# G-103M-20190827.net
KiCad netlist of a schematic drawn in Altium Designer
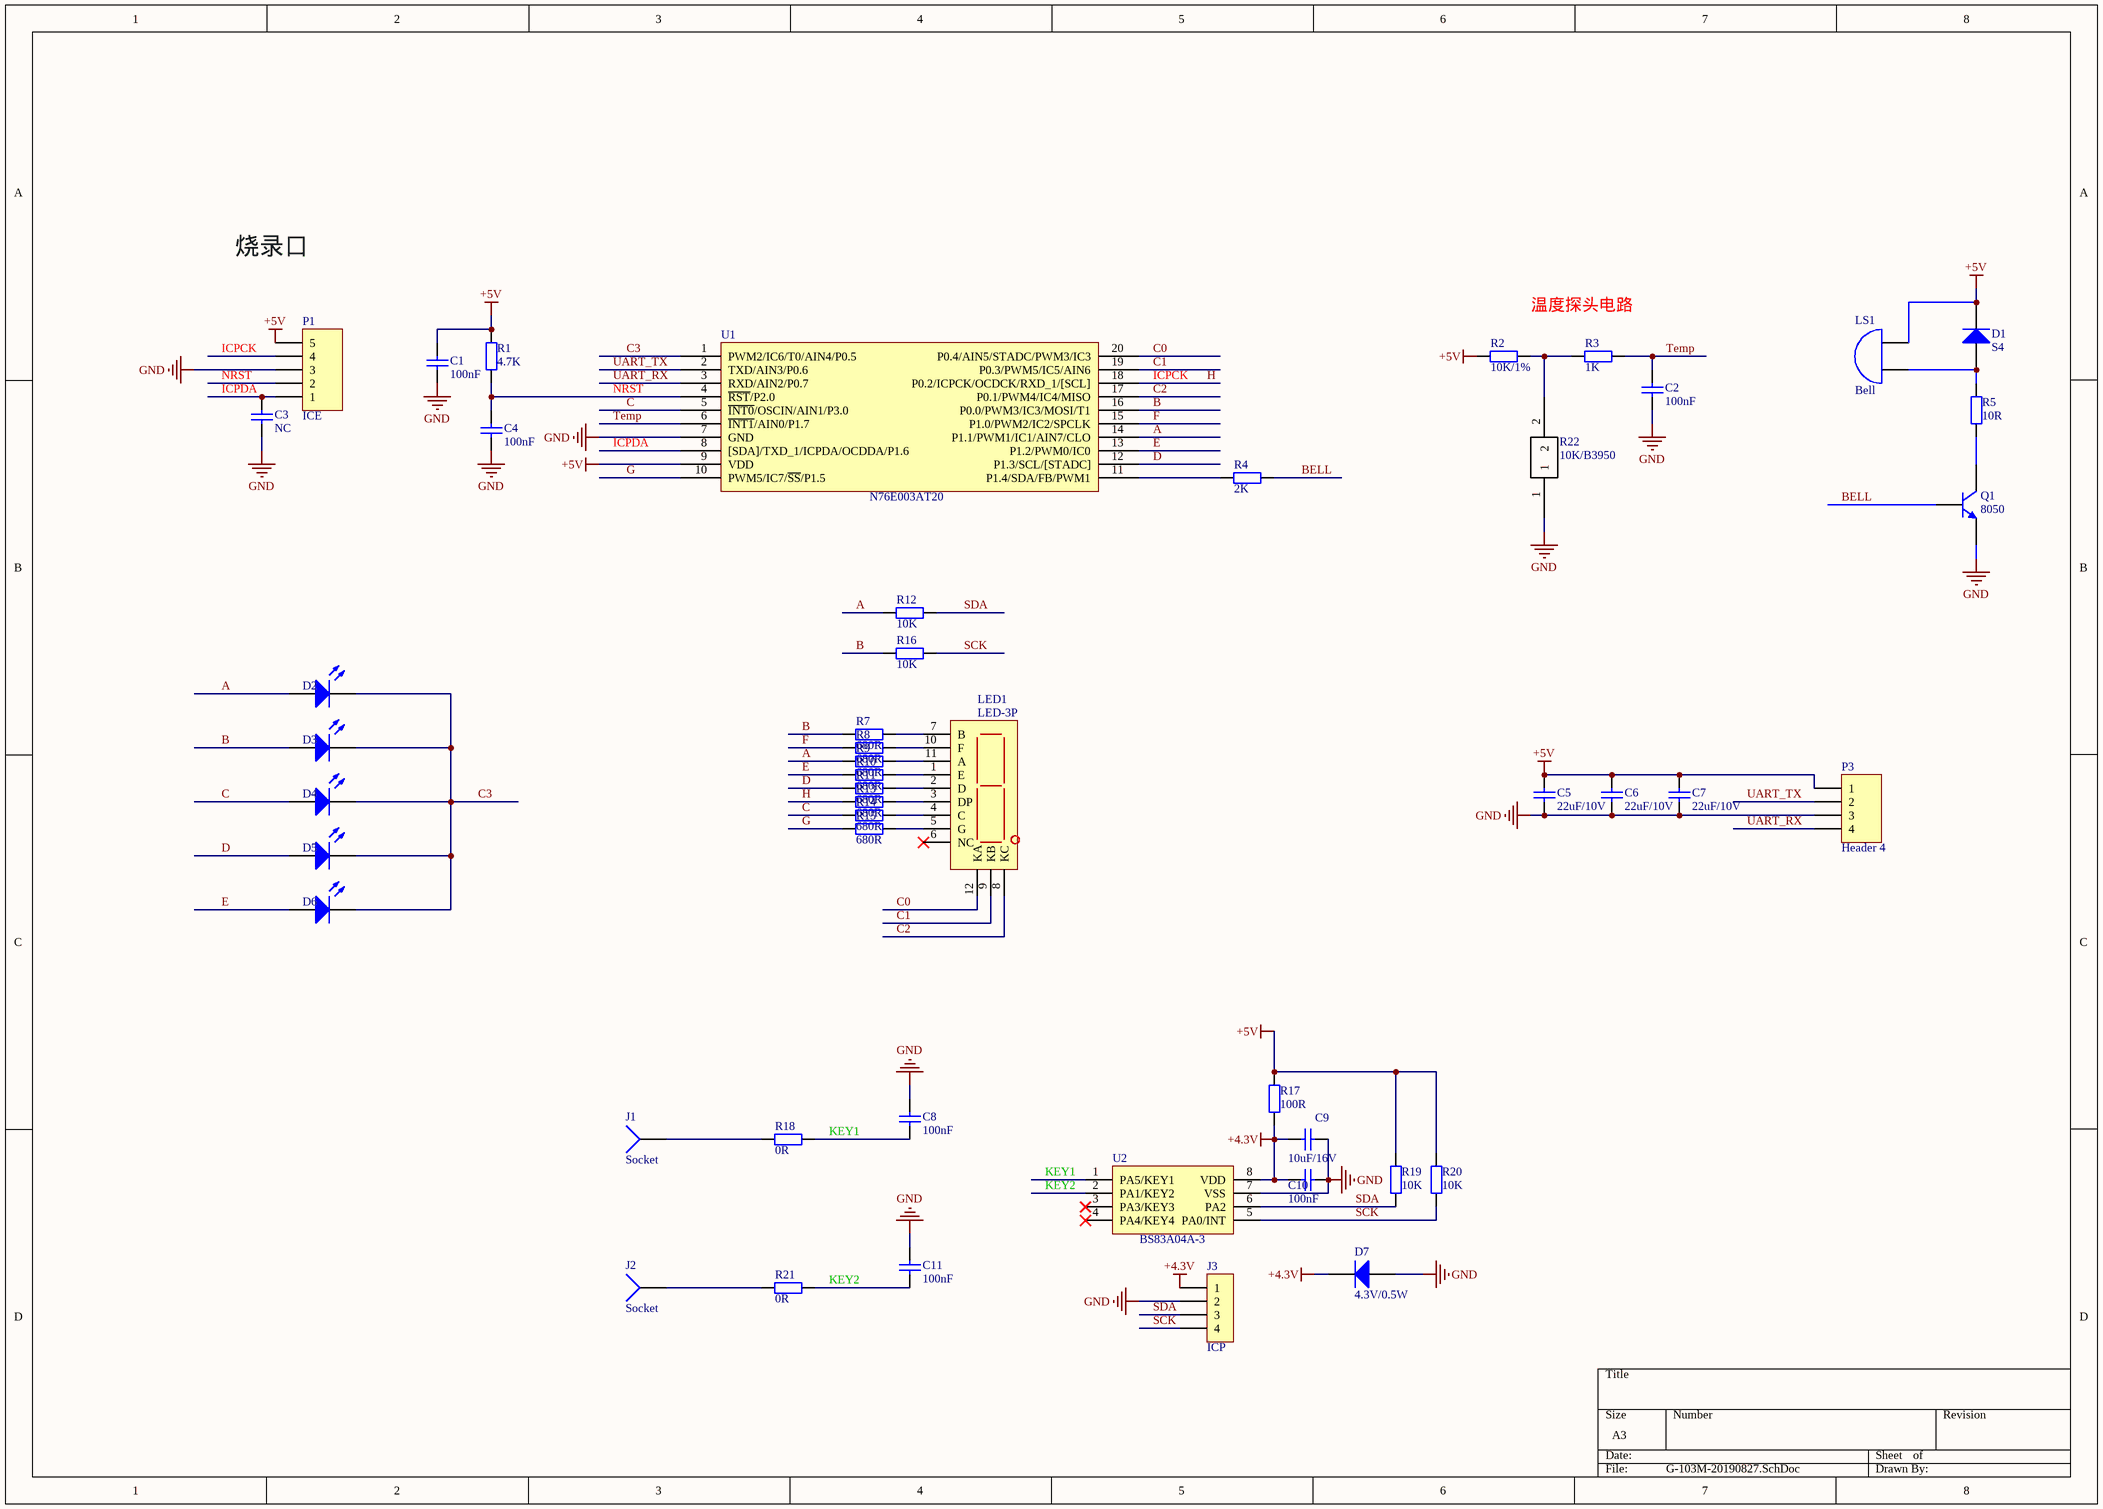
[diagram p0: G-103M-20190827.SchDoc]

(export (version "E")
  (design (tool "Eeschema 10.0.6"))
  (components
    (comp (ref "C1")
      (value "100nF")
      (footprint "SMD-0603")
      (description "Capacitor")
      (fields (field (name "Comment") "Cap") (field (name "PUBLISHER") "Altium Limited"))
      (libsource (lib "Miscellaneous Devices") (part "Cap"))
    )
    (comp (ref "C2")
      (value "100nF")
      (footprint "SMD-0603")
      (description "Capacitor")
      (fields (field (name "PUBLISHER") "Altium Limited"))
      (libsource (lib "Miscellaneous Devices") (part "Cap"))
    )
    (comp (ref "C3")
      (value "NC")
      (footprint "SMD-0603")
      (description "Capacitor")
      (fields (field (name "PUBLISHER") "Altium Limited"))
      (libsource (lib "Miscellaneous Devices") (part "Cap"))
    )
    (comp (ref "C4")
      (value "100nF")
      (footprint "SMD-0603")
      (description "Capacitor")
      (fields (field (name "Comment") "Cap") (field (name "PUBLISHER") "Altium Limited"))
      (libsource (lib "Miscellaneous Devices") (part "Cap"))
    )
    (comp (ref "C5")
      (value "22uF/10V")
      (footprint "SMD-0603")
      (description "Capacitor")
      (fields (field (name "PUBLISHER") "Altium Limited"))
      (libsource (lib "Miscellaneous Devices") (part "Cap"))
    )
    (comp (ref "C6")
      (value "22uF/10V")
      (footprint "SMD-0603")
      (description "Capacitor")
      (fields (field (name "PUBLISHER") "Altium Limited"))
      (libsource (lib "Miscellaneous Devices") (part "Cap"))
    )
    (comp (ref "C7")
      (value "22uF/10V")
      (footprint "SMD-0603")
      (description "Capacitor")
      (fields (field (name "PUBLISHER") "Altium Limited"))
      (libsource (lib "Miscellaneous Devices") (part "Cap"))
    )
    (comp (ref "C8")
      (value "100nF")
      (footprint "SMD-0603")
      (description "Capacitor (Semiconductor SIM Model)")
      (fields (field (name "PUBLISHER") "Altium Limited"))
      (libsource (lib "Miscellaneous Devices") (part "Cap Semi"))
    )
    (comp (ref "C9")
      (value "10uF/16V")
      (footprint "SMD-0603")
      (description "Capacitor (Semiconductor SIM Model)")
      (fields (field (name "PUBLISHER") "Altium Limited"))
      (libsource (lib "Miscellaneous Devices") (part "Cap Semi"))
    )
    (comp (ref "C10")
      (value "100nF")
      (footprint "SMD-0603")
      (description "Capacitor (Semiconductor SIM Model)")
      (fields (field (name "PUBLISHER") "Altium Limited"))
      (libsource (lib "Miscellaneous Devices") (part "Cap Semi"))
    )
    (comp (ref "C11")
      (value "100nF")
      (footprint "SMD-0603")
      (description "Capacitor (Semiconductor SIM Model)")
      (fields (field (name "PUBLISHER") "Altium Limited"))
      (libsource (lib "Miscellaneous Devices") (part "Cap Semi"))
    )
    (comp (ref "D1")
      (value "S4")
      (footprint "SOD123")
      (description "1 Amp General Purpose Rectifier")
      (fields (field (name "PUBLISHER") "Altium Limited"))
      (libsource (lib "Miscellaneous Devices") (part "Diode 1N4007"))
    )
    (comp (ref "D2")
      (value "~")
      (footprint "LED-3MM")
      (description "Typical RED GaAs LED")
      (fields (field (name "PUBLISHER") "Altium Limited"))
      (libsource (lib "Miscellaneous Devices") (part "LED1"))
    )
    (comp (ref "D3")
      (value "~")
      (footprint "LED-3MM")
      (description "Typical RED GaAs LED")
      (fields (field (name "PUBLISHER") "Altium Limited"))
      (libsource (lib "Miscellaneous Devices") (part "LED1"))
    )
    (comp (ref "D4")
      (value "~")
      (footprint "LED-3MM")
      (description "Typical RED GaAs LED")
      (fields (field (name "PUBLISHER") "Altium Limited"))
      (libsource (lib "Miscellaneous Devices") (part "LED1"))
    )
    (comp (ref "D5")
      (value "~")
      (footprint "LED-3MM")
      (description "Typical RED GaAs LED")
      (fields (field (name "PUBLISHER") "Altium Limited"))
      (libsource (lib "Miscellaneous Devices") (part "LED1"))
    )
    (comp (ref "D6")
      (value "~")
      (footprint "LED-3MM")
      (description "Typical RED GaAs LED")
      (fields (field (name "PUBLISHER") "Altium Limited"))
      (libsource (lib "Miscellaneous Devices") (part "LED1"))
    )
    (comp (ref "D7")
      (value "4.3V/0.5W")
      (footprint "SOD123")
      (description "1 Amp General Purpose Rectifier")
      (fields (field (name "PUBLISHER") "Altium Limited"))
      (libsource (lib "Miscellaneous Devices") (part "Diode 1N4007"))
    )
    (comp (ref "J1")
      (value "Socket")
      (footprint "KEY-C1")
      (fields (field (name "PUBLISHER") "Altium Limited"))
      (libsource (lib "Miscellaneous Connectors") (part "Socket"))
    )
    (comp (ref "J2")
      (value "Socket")
      (footprint "KEY-C1")
      (fields (field (name "PUBLISHER") "Altium Limited"))
      (libsource (lib "Miscellaneous Connectors") (part "Socket"))
    )
    (comp (ref "J3")
      (value "ICP")
      (footprint "HDR1X4")
      (description "Connector")
      (libsource (lib "SCH") (part "CON4"))
    )
    (comp (ref "LED1")
      (value "LED-3P")
      (footprint "LED363")
      (description "LED")
      (libsource (lib "MJRS0-20150109") (part "LED-3P"))
    )
    (comp (ref "LS1")
      (value "Bell")
      (footprint "BUZ-2-5V")
      (description "Electrical Bell")
      (fields (field (name "PUBLISHER") "Altium Limited"))
      (libsource (lib "Miscellaneous Devices") (part "Bell"))
    )
    (comp (ref "P1")
      (value "ICE")
      (footprint "HDR1X5")
      (description "Header, 5-Pin")
      (fields (field (name "PUBLISHER") "Altium Limited"))
      (libsource (lib "Miscellaneous Connectors") (part "Header 5"))
    )
    (comp (ref "P3")
      (value "Header 4")
      (footprint "2.0-4P")
      (description "Header, 4-Pin")
      (fields (field (name "PUBLISHER") "Altium Limited"))
      (libsource (lib "Miscellaneous Connectors") (part "Header 4"))
    )
    (comp (ref "Q1")
      (value "8050")
      (footprint "SOT-23E2")
      (description "NPN General Purpose Amplifier")
      (fields (field (name "PUBLISHER") "Altium Limited"))
      (libsource (lib "接收机") (part "2N3904"))
    )
    (comp (ref "R1")
      (value "4.7K")
      (footprint "SMD-0603")
      (description "Resistor")
      (fields (field (name "Comment") "Res2") (field (name "PUBLISHER") "Altium Limited"))
      (libsource (lib "") (part "Res2_3"))
    )
    (comp (ref "R2")
      (value "10K/1%")
      (footprint "SMD-0603")
      (description "Resistor")
      (fields (field (name "PUBLISHER") "Altium Limited"))
      (libsource (lib "Miscellaneous Devices") (part "Res2"))
    )
    (comp (ref "R3")
      (value "1K")
      (footprint "SMD-0603")
      (description "Resistor")
      (fields (field (name "PUBLISHER") "Altium Limited"))
      (libsource (lib "Miscellaneous Devices") (part "Res2"))
    )
    (comp (ref "R4")
      (value "2K")
      (footprint "SMD-0603")
      (description "Resistor")
      (fields (field (name "PUBLISHER") "Altium Limited"))
      (libsource (lib "Miscellaneous Devices") (part "Res2"))
    )
    (comp (ref "R5")
      (value "10R")
      (footprint "SMD-0603")
      (description "Resistor")
      (fields (field (name "PUBLISHER") "Altium Limited"))
      (libsource (lib "") (part "Res2_3"))
    )
    (comp (ref "R7")
      (value "680R")
      (footprint "SMD-0603")
      (description "Resistor")
      (fields (field (name "PUBLISHER") "Altium Limited"))
      (libsource (lib "Miscellaneous Devices") (part "Res2"))
    )
    (comp (ref "R8")
      (value "680R")
      (footprint "SMD-0603")
      (description "Resistor")
      (fields (field (name "PUBLISHER") "Altium Limited"))
      (libsource (lib "Miscellaneous Devices") (part "Res2"))
    )
    (comp (ref "R9")
      (value "680R")
      (footprint "SMD-0603")
      (description "Resistor")
      (fields (field (name "PUBLISHER") "Altium Limited"))
      (libsource (lib "Miscellaneous Devices") (part "Res2"))
    )
    (comp (ref "R10")
      (value "680R")
      (footprint "SMD-0603")
      (description "Resistor")
      (fields (field (name "PUBLISHER") "Altium Limited"))
      (libsource (lib "Miscellaneous Devices") (part "Res2"))
    )
    (comp (ref "R11")
      (value "680R")
      (footprint "SMD-0603")
      (description "Resistor")
      (fields (field (name "PUBLISHER") "Altium Limited"))
      (libsource (lib "Miscellaneous Devices") (part "Res2"))
    )
    (comp (ref "R12")
      (value "10K")
      (footprint "SMD-0603")
      (description "Resistor")
      (fields (field (name "PUBLISHER") "Altium Limited"))
      (libsource (lib "") (part "Res2_2"))
    )
    (comp (ref "R13")
      (value "680R")
      (footprint "SMD-0603")
      (description "Resistor")
      (fields (field (name "PUBLISHER") "Altium Limited"))
      (libsource (lib "Miscellaneous Devices") (part "Res2"))
    )
    (comp (ref "R14")
      (value "680R")
      (footprint "SMD-0603")
      (description "Resistor")
      (fields (field (name "PUBLISHER") "Altium Limited"))
      (libsource (lib "Miscellaneous Devices") (part "Res2"))
    )
    (comp (ref "R15")
      (value "680R")
      (footprint "SMD-0603")
      (description "Resistor")
      (fields (field (name "PUBLISHER") "Altium Limited"))
      (libsource (lib "Miscellaneous Devices") (part "Res2"))
    )
    (comp (ref "R16")
      (value "10K")
      (footprint "SMD-0603")
      (description "Resistor")
      (fields (field (name "PUBLISHER") "Altium Limited"))
      (libsource (lib "") (part "Res2_2"))
    )
    (comp (ref "R17")
      (value "100R")
      (footprint "SMD-0603")
      (description "Resistor")
      (fields (field (name "PUBLISHER") "Altium Limited"))
      (libsource (lib "") (part "Res2_3"))
    )
    (comp (ref "R18")
      (value "0R")
      (footprint "SMD-0603")
      (description "Resistor")
      (fields (field (name "PUBLISHER") "Altium Limited"))
      (libsource (lib "Miscellaneous Devices") (part "Res2"))
    )
    (comp (ref "R19")
      (value "10K")
      (footprint "SMD-0603")
      (description "Resistor")
      (fields (field (name "PUBLISHER") "Altium Limited"))
      (libsource (lib "") (part "Res2_1"))
    )
    (comp (ref "R20")
      (value "10K")
      (footprint "SMD-0603")
      (description "Resistor")
      (fields (field (name "PUBLISHER") "Altium Limited"))
      (libsource (lib "") (part "Res2_1"))
    )
    (comp (ref "R21")
      (value "0R")
      (footprint "SMD-0603")
      (description "Resistor")
      (fields (field (name "PUBLISHER") "Altium Limited"))
      (libsource (lib "Miscellaneous Devices") (part "Res2"))
    )
    (comp (ref "R22")
      (value "10K/B3950")
      (footprint "SMD-0603")
      (libsource (lib "Integrated_Library") (part "10K/B3950"))
    )
    (comp (ref "U1")
      (value "N76E003AT20")
      (footprint "TSSOP-20")
      (libsource (lib "AQ405_Power") (part "N76E003AT20"))
    )
    (comp (ref "U2") (value "BS83A04A-3") (footprint "SOP8") (libsource (lib "SCH") (part "BS83A04A-3")))
  )
  (nets
    (net (code "1") (name "+4.3V") (class "Default")
      (node (ref "C10") (pin "1") (pinfunction "1_1") (pintype "passive"))
      (node (ref "C9") (pin "1") (pinfunction "1_1") (pintype "passive"))
      (node (ref "D7") (pin "2") (pinfunction "K_2") (pintype "passive"))
      (node (ref "J3") (pin "1") (pinfunction "1_1") (pintype "passive"))
      (node (ref "R17") (pin "2") (pinfunction "2_2") (pintype "passive"))
      (node (ref "U2") (pin "8") (pinfunction "VDD_8") (pintype "passive"))
    )
    (net (code "2") (name "+5V") (class "Default")
      (node (ref "C1") (pin "2") (pinfunction "2_2") (pintype "passive"))
      (node (ref "C5") (pin "2") (pinfunction "2_2") (pintype "passive"))
      (node (ref "C6") (pin "2") (pinfunction "2_2") (pintype "passive"))
      (node (ref "C7") (pin "2") (pinfunction "2_2") (pintype "passive"))
      (node (ref "D1") (pin "2") (pinfunction "K_2") (pintype "passive"))
      (node (ref "LS1") (pin "1") (pinfunction "A_1") (pintype "passive"))
      (node (ref "P1") (pin "5") (pinfunction "5_5") (pintype "passive"))
      (node (ref "P3") (pin "1") (pinfunction "1_1") (pintype "passive"))
      (node (ref "R1") (pin "1") (pinfunction "1_1") (pintype "passive"))
      (node (ref "R17") (pin "1") (pinfunction "1_1") (pintype "passive"))
      (node (ref "R19") (pin "2") (pinfunction "2_2") (pintype "passive"))
      (node (ref "R2") (pin "2") (pinfunction "2_2") (pintype "passive"))
      (node (ref "R20") (pin "2") (pinfunction "2_2") (pintype "passive"))
      (node (ref "U1") (pin "9") (pinfunction "VDD_9") (pintype "passive"))
    )
    (net (code "3") (name "/A") (class "Default")
      (node (ref "D2") (pin "1") (pinfunction "A_1") (pintype "passive"))
      (node (ref "R12") (pin "1") (pinfunction "1_1") (pintype "passive"))
      (node (ref "R9") (pin "2") (pinfunction "2_2") (pintype "passive"))
      (node (ref "U1") (pin "14") (pinfunction "P1.1/PWM1/IC1/AIN7/CLO_14") (pintype "passive"))
    )
    (net (code "4") (name "/B") (class "Default")
      (node (ref "D3") (pin "1") (pinfunction "A_1") (pintype "passive"))
      (node (ref "R16") (pin "1") (pinfunction "1_1") (pintype "passive"))
      (node (ref "R7") (pin "2") (pinfunction "2_2") (pintype "passive"))
      (node (ref "U1") (pin "16") (pinfunction "P0.0/PWM3/IC3/MOSI/T1_16") (pintype "passive"))
    )
    (net (code "5") (name "/BELL") (class "Default")
      (node (ref "Q1") (pin "B") (pinfunction "B_B") (pintype "passive"))
      (node (ref "R4") (pin "1") (pinfunction "1_1") (pintype "passive"))
    )
    (net (code "6") (name "/C") (class "Default")
      (node (ref "D4") (pin "1") (pinfunction "A_1") (pintype "passive"))
      (node (ref "R14") (pin "2") (pinfunction "2_2") (pintype "passive"))
      (node (ref "U1") (pin "5") (pinfunction "~{INT0}/OSCIN/AIN1/P3.0_5") (pintype "passive"))
    )
    (net (code "7") (name "/C0") (class "Default")
      (node (ref "LED1") (pin "12") (pinfunction "KA_12") (pintype "passive"))
      (node (ref "U1") (pin "20") (pinfunction "P0.4/AIN5/STADC/PWM3/IC3_20") (pintype "passive"))
    )
    (net (code "8") (name "/C1") (class "Default")
      (node (ref "LED1") (pin "9") (pinfunction "KB_9") (pintype "passive"))
      (node (ref "U1") (pin "19") (pinfunction "P0.3/PWM5/IC5/AIN6_19") (pintype "passive"))
    )
    (net (code "9") (name "/C2") (class "Default")
      (node (ref "LED1") (pin "8") (pinfunction "KC_8") (pintype "passive"))
      (node (ref "U1") (pin "17") (pinfunction "P0.1/PWM4/IC4/MISO_17") (pintype "passive"))
    )
    (net (code "10") (name "/C3") (class "Default")
      (node (ref "D2") (pin "2") (pinfunction "K_2") (pintype "passive"))
      (node (ref "D3") (pin "2") (pinfunction "K_2") (pintype "passive"))
      (node (ref "D4") (pin "2") (pinfunction "K_2") (pintype "passive"))
      (node (ref "D5") (pin "2") (pinfunction "K_2") (pintype "passive"))
      (node (ref "D6") (pin "2") (pinfunction "K_2") (pintype "passive"))
      (node (ref "U1") (pin "1") (pinfunction "PWM2/IC6/T0/AIN4/P0.5_1") (pintype "passive"))
    )
    (net (code "11") (name "/D") (class "Default")
      (node (ref "D5") (pin "1") (pinfunction "A_1") (pintype "passive"))
      (node (ref "R11") (pin "2") (pinfunction "2_2") (pintype "passive"))
      (node (ref "U1") (pin "12") (pinfunction "P1.3/SCL/[STADC]_12") (pintype "passive"))
    )
    (net (code "12") (name "/E") (class "Default")
      (node (ref "D6") (pin "1") (pinfunction "A_1") (pintype "passive"))
      (node (ref "R10") (pin "2") (pinfunction "2_2") (pintype "passive"))
      (node (ref "U1") (pin "13") (pinfunction "P1.2/PWM0/IC0_13") (pintype "passive"))
    )
    (net (code "13") (name "/F") (class "Default")
      (node (ref "R8") (pin "2") (pinfunction "2_2") (pintype "passive"))
      (node (ref "U1") (pin "15") (pinfunction "P1.0/PWM2/IC2/SPCLK_15") (pintype "passive"))
    )
    (net (code "14") (name "/G") (class "Default")
      (node (ref "R15") (pin "2") (pinfunction "2_2") (pintype "passive"))
      (node (ref "U1") (pin "10") (pinfunction "PWM5/IC7/~{SS}/P1.5_10") (pintype "passive"))
    )
    (net (code "15") (name "/H") (class "Default")
      (node (ref "P1") (pin "4") (pinfunction "4_4") (pintype "passive"))
      (node (ref "R13") (pin "2") (pinfunction "2_2") (pintype "passive"))
      (node (ref "U1") (pin "18") (pinfunction "P0.2/ICPCK/OCDCK/RXD_1/[SCL]_18") (pintype "passive"))
    )
    (net (code "16") (name "/ICPDA") (class "Default")
      (node (ref "C3") (pin "1") (pinfunction "1_1") (pintype "passive"))
      (node (ref "P1") (pin "1") (pinfunction "1_1") (pintype "passive"))
      (node (ref "U1") (pin "8") (pinfunction "[SDA]/TXD_1/ICPDA/OCDDA/P1.6_8") (pintype "passive"))
    )
    (net (code "17") (name "/KEY1") (class "Default")
      (node (ref "C8") (pin "1") (pinfunction "1_1") (pintype "passive"))
      (node (ref "R18") (pin "1") (pinfunction "1_1") (pintype "passive"))
      (node (ref "U2") (pin "1") (pinfunction "PA5/KEY1_1") (pintype "passive"))
    )
    (net (code "18") (name "/KEY2") (class "Default")
      (node (ref "C11") (pin "1") (pinfunction "1_1") (pintype "passive"))
      (node (ref "R21") (pin "1") (pinfunction "1_1") (pintype "passive"))
      (node (ref "U2") (pin "2") (pinfunction "PA1/KEY2_2") (pintype "passive"))
    )
    (net (code "19") (name "/NRST") (class "Default")
      (node (ref "C4") (pin "2") (pinfunction "2_2") (pintype "passive"))
      (node (ref "P1") (pin "2") (pinfunction "2_2") (pintype "passive"))
      (node (ref "R1") (pin "2") (pinfunction "2_2") (pintype "passive"))
      (node (ref "U1") (pin "4") (pinfunction "~{RST}/P2.0_4") (pintype "passive"))
    )
    (net (code "20") (name "/SCK") (class "Default")
      (node (ref "J3") (pin "4") (pinfunction "4_4") (pintype "passive"))
      (node (ref "R16") (pin "2") (pinfunction "2_2") (pintype "passive"))
      (node (ref "R20") (pin "1") (pinfunction "1_1") (pintype "passive"))
      (node (ref "U2") (pin "5") (pinfunction "PA0/INT_5") (pintype "passive"))
    )
    (net (code "21") (name "/SDA") (class "Default")
      (node (ref "J3") (pin "3") (pinfunction "3_3") (pintype "passive"))
      (node (ref "R12") (pin "2") (pinfunction "2_2") (pintype "passive"))
      (node (ref "R19") (pin "1") (pinfunction "1_1") (pintype "passive"))
      (node (ref "U2") (pin "6") (pinfunction "PA2_6") (pintype "passive"))
    )
    (net (code "22") (name "/Temp") (class "Default")
      (node (ref "C2") (pin "2") (pinfunction "2_2") (pintype "passive"))
      (node (ref "R3") (pin "1") (pinfunction "1_1") (pintype "passive"))
      (node (ref "U1") (pin "6") (pinfunction "~{INT1}/AIN0/P1.7_6") (pintype "passive"))
    )
    (net (code "23") (name "/UART_RX") (class "Default")
      (node (ref "P3") (pin "4") (pinfunction "4_4") (pintype "passive"))
      (node (ref "U1") (pin "3") (pinfunction "RXD/AIN2/P0.7_3") (pintype "passive"))
    )
    (net (code "24") (name "/UART_TX") (class "Default")
      (node (ref "P3") (pin "2") (pinfunction "2_2") (pintype "passive"))
      (node (ref "U1") (pin "2") (pinfunction "TXD/AIN3/P0.6_2") (pintype "passive"))
    )
    (net (code "25") (name "GND") (class "Default")
      (node (ref "C1") (pin "1") (pinfunction "1_1") (pintype "passive"))
      (node (ref "C10") (pin "2") (pinfunction "2_2") (pintype "passive"))
      (node (ref "C11") (pin "2") (pinfunction "2_2") (pintype "passive"))
      (node (ref "C2") (pin "1") (pinfunction "1_1") (pintype "passive"))
      (node (ref "C3") (pin "2") (pinfunction "2_2") (pintype "passive"))
      (node (ref "C4") (pin "1") (pinfunction "1_1") (pintype "passive"))
      (node (ref "C5") (pin "1") (pinfunction "1_1") (pintype "passive"))
      (node (ref "C6") (pin "1") (pinfunction "1_1") (pintype "passive"))
      (node (ref "C7") (pin "1") (pinfunction "1_1") (pintype "passive"))
      (node (ref "C8") (pin "2") (pinfunction "2_2") (pintype "passive"))
      (node (ref "C9") (pin "2") (pinfunction "2_2") (pintype "passive"))
      (node (ref "D7") (pin "1") (pinfunction "A_1") (pintype "passive"))
      (node (ref "J3") (pin "2") (pinfunction "2_2") (pintype "passive"))
      (node (ref "P1") (pin "3") (pinfunction "3_3") (pintype "passive"))
      (node (ref "P3") (pin "3") (pinfunction "3_3") (pintype "passive"))
      (node (ref "Q1") (pin "E") (pinfunction "E_E") (pintype "passive"))
      (node (ref "R22") (pin "1") (pinfunction "1_1") (pintype "passive"))
      (node (ref "U1") (pin "7") (pinfunction "GND_7") (pintype "passive"))
      (node (ref "U2") (pin "7") (pinfunction "VSS_7") (pintype "passive"))
    )
    (net (code "26") (name "Net-(D1-A)") (class "Default")
      (node (ref "D1") (pin "1") (pinfunction "A_1") (pintype "passive"))
      (node (ref "LS1") (pin "2") (pinfunction "B_2") (pintype "passive"))
      (node (ref "R5") (pin "1") (pinfunction "1_1") (pintype "passive"))
    )
    (net (code "27") (name "Net-(J1-Pad1)") (class "Default")
      (node (ref "J1") (pin "1") (pinfunction "1_1") (pintype "passive"))
      (node (ref "R18") (pin "2") (pinfunction "2_2") (pintype "passive"))
    )
    (net (code "28") (name "Net-(J2-Pad1)") (class "Default")
      (node (ref "J2") (pin "1") (pinfunction "1_1") (pintype "passive"))
      (node (ref "R21") (pin "2") (pinfunction "2_2") (pintype "passive"))
    )
    (net (code "29") (name "Net-(LED1-A)") (class "Default")
      (node (ref "LED1") (pin "11") (pinfunction "A_11") (pintype "passive"))
      (node (ref "R9") (pin "1") (pinfunction "1_1") (pintype "passive"))
    )
    (net (code "30") (name "Net-(LED1-B)") (class "Default")
      (node (ref "LED1") (pin "7") (pinfunction "B_7") (pintype "passive"))
      (node (ref "R7") (pin "1") (pinfunction "1_1") (pintype "passive"))
    )
    (net (code "31") (name "Net-(LED1-C)") (class "Default")
      (node (ref "LED1") (pin "4") (pinfunction "C_4") (pintype "passive"))
      (node (ref "R14") (pin "1") (pinfunction "1_1") (pintype "passive"))
    )
    (net (code "32") (name "Net-(LED1-D)") (class "Default")
      (node (ref "LED1") (pin "2") (pinfunction "D_2") (pintype "passive"))
      (node (ref "R11") (pin "1") (pinfunction "1_1") (pintype "passive"))
    )
    (net (code "33") (name "Net-(LED1-DP)") (class "Default")
      (node (ref "LED1") (pin "3") (pinfunction "DP_3") (pintype "passive"))
      (node (ref "R13") (pin "1") (pinfunction "1_1") (pintype "passive"))
    )
    (net (code "34") (name "Net-(LED1-E)") (class "Default")
      (node (ref "LED1") (pin "1") (pinfunction "E_1") (pintype "passive"))
      (node (ref "R10") (pin "1") (pinfunction "1_1") (pintype "passive"))
    )
    (net (code "35") (name "Net-(LED1-F)") (class "Default")
      (node (ref "LED1") (pin "10") (pinfunction "F_10") (pintype "passive"))
      (node (ref "R8") (pin "1") (pinfunction "1_1") (pintype "passive"))
    )
    (net (code "36") (name "Net-(LED1-G)") (class "Default")
      (node (ref "LED1") (pin "5") (pinfunction "G_5") (pintype "passive"))
      (node (ref "R15") (pin "1") (pinfunction "1_1") (pintype "passive"))
    )
    (net (code "37") (name "Net-(Q1-PadC)") (class "Default")
      (node (ref "Q1") (pin "C") (pinfunction "C_C") (pintype "passive"))
      (node (ref "R5") (pin "2") (pinfunction "2_2") (pintype "passive"))
    )
    (net (code "38") (name "Net-(R2-Pad1)") (class "Default")
      (node (ref "R2") (pin "1") (pinfunction "1_1") (pintype "passive"))
      (node (ref "R22") (pin "2") (pinfunction "2_2") (pintype "passive"))
      (node (ref "R3") (pin "2") (pinfunction "2_2") (pintype "passive"))
    )
    (net (code "39") (name "Net-(U1-P1.4{slash}SDA{slash}FB{slash}PWM1)") (class "Default")
      (node (ref "R4") (pin "2") (pinfunction "2_2") (pintype "passive"))
      (node (ref "U1") (pin "11") (pinfunction "P1.4/SDA/FB/PWM1_11") (pintype "passive"))
    )
    (net (code "40") (name "unconnected-(LED1-NC-Pad6)") (class "Default")
      (node (ref "LED1") (pin "6") (pinfunction "NC_6") (pintype "passive+no_connect"))
    )
    (net (code "41") (name "unconnected-(U2-PA3{slash}KEY3-Pad3)") (class "Default")
      (node (ref "U2") (pin "3") (pinfunction "PA3/KEY3_3") (pintype "passive+no_connect"))
    )
    (net (code "42") (name "unconnected-(U2-PA4{slash}KEY4-Pad4)") (class "Default")
      (node (ref "U2") (pin "4") (pinfunction "PA4/KEY4_4") (pintype "passive+no_connect"))
    )
  )
)
